# opl2msx_v1_1.net
KiCad netlist of a schematic drawn in EAGLE
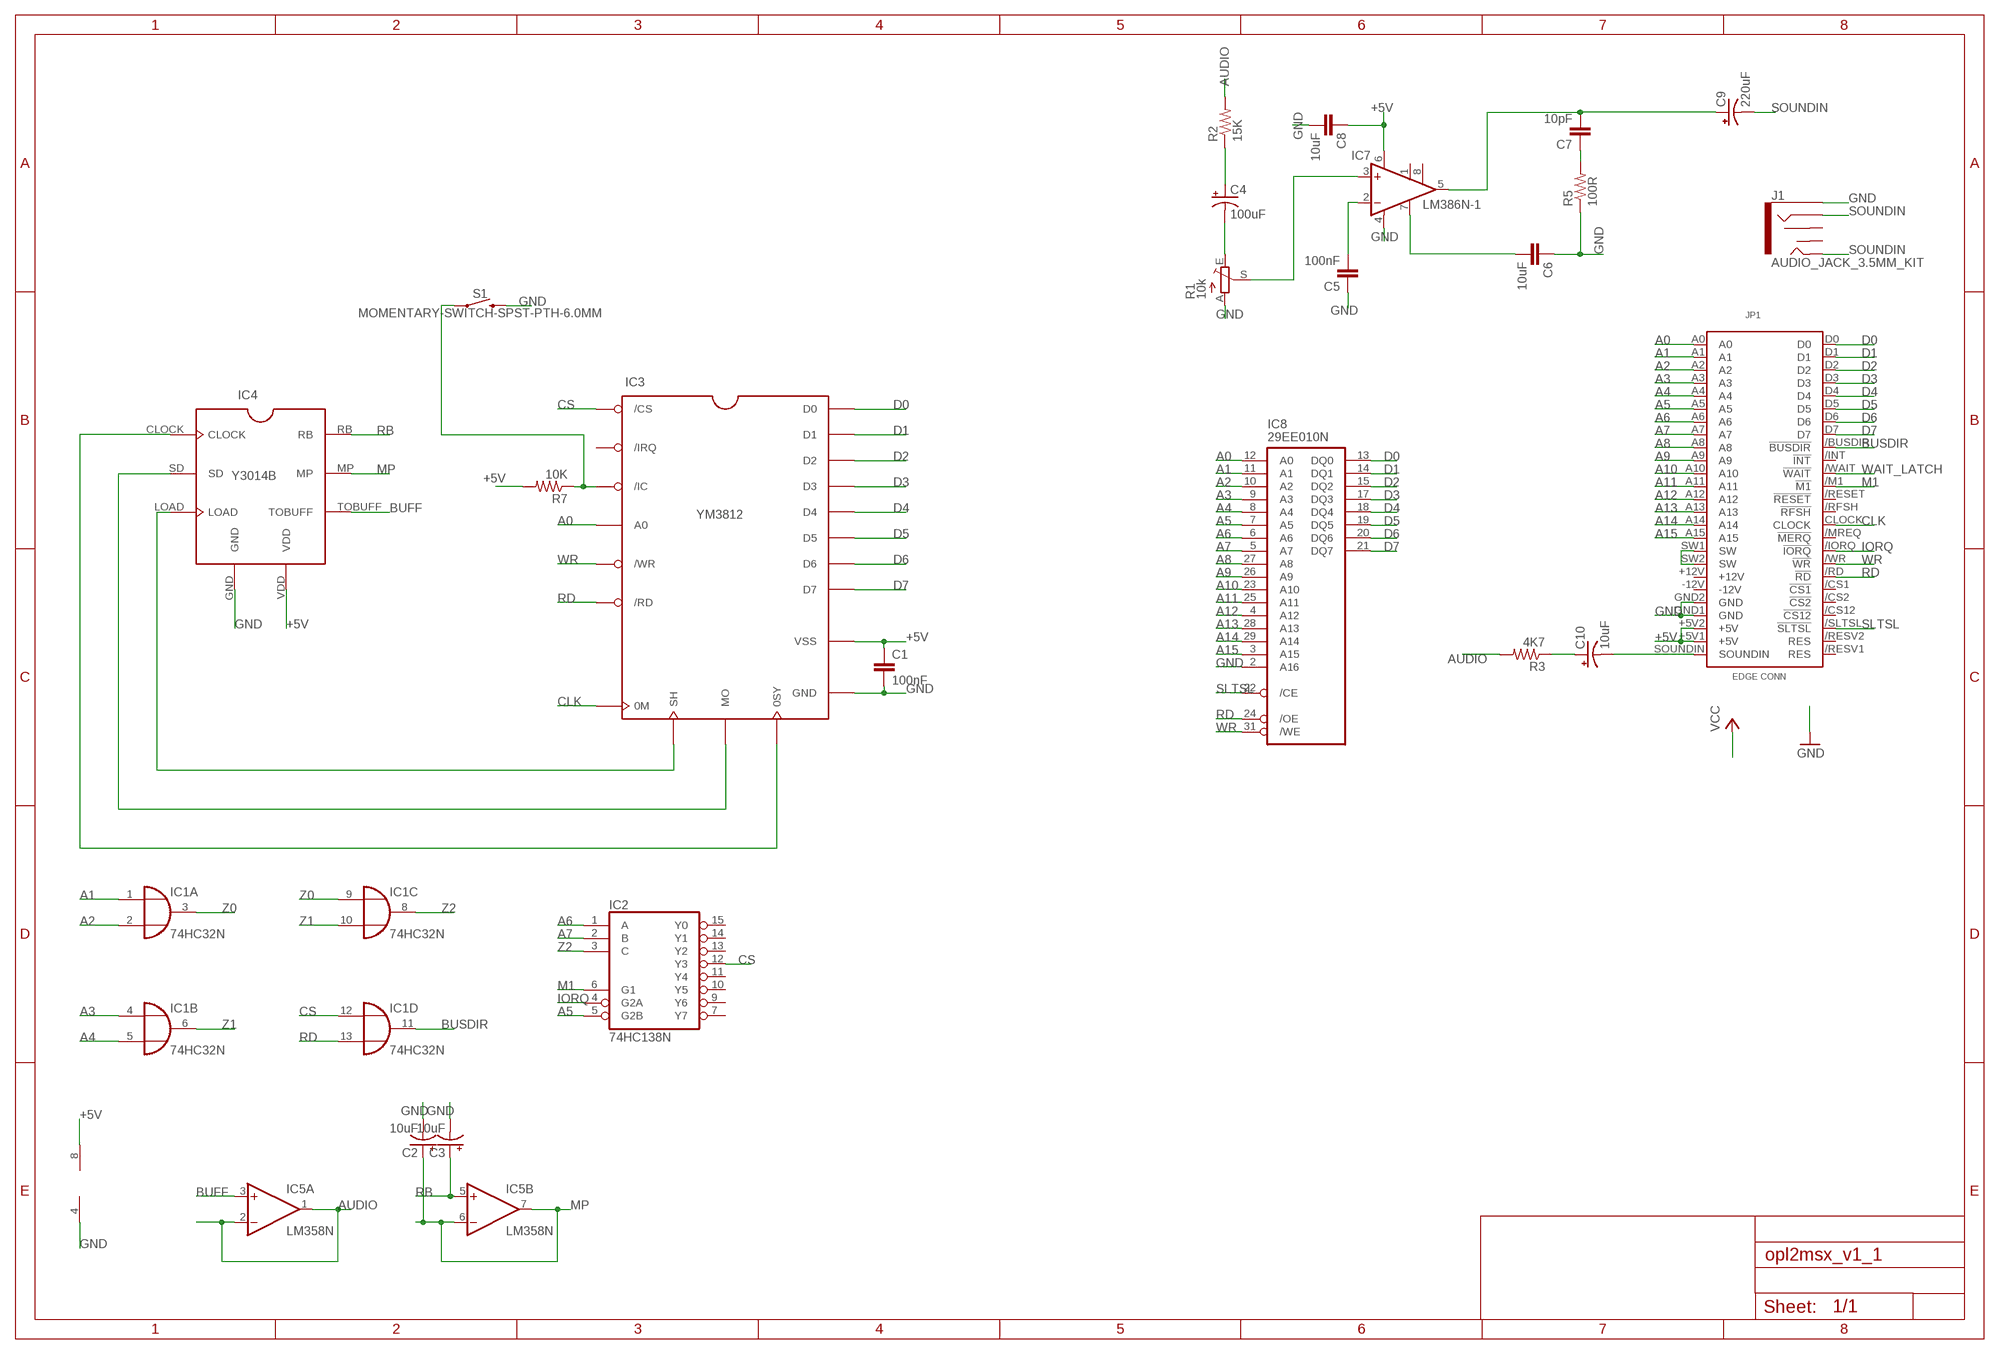
[diagram p0: schematic, sheet 1]

(export (version "E")
  (design (tool "Eeschema 10.0.6"))
  (components
    (comp (ref "C1")
      (value "100nF")
      (footprint "eagle-import:C050-024X044")
      (libsource (lib "eagle-import") (part "C-EU050-024X044"))
    )
    (comp (ref "C2")
      (value "10uF")
      (footprint "eagle-import:E2,5-6")
      (libsource (lib "eagle-import") (part "CPOL-USE2.5-6"))
    )
    (comp (ref "C3")
      (value "10uF")
      (footprint "eagle-import:E2,5-6")
      (libsource (lib "eagle-import") (part "CPOL-USE2.5-6"))
    )
    (comp (ref "C4")
      (value "100uF")
      (footprint "eagle-import:E2,5-6")
      (libsource (lib "eagle-import") (part "CPOL-USE2.5-6"))
    )
    (comp (ref "C5")
      (value "100nF")
      (footprint "eagle-import:C050-024X044")
      (libsource (lib "eagle-import") (part "C-EU050-024X044"))
    )
    (comp (ref "C6")
      (value "10uF")
      (footprint "eagle-import:C050-024X044")
      (libsource (lib "eagle-import") (part "C-EU050-024X044"))
    )
    (comp (ref "C7")
      (value "10pF")
      (footprint "eagle-import:C050-024X044")
      (libsource (lib "eagle-import") (part "C-EU050-024X044"))
    )
    (comp (ref "C8")
      (value "10uF")
      (footprint "eagle-import:C050-024X044")
      (libsource (lib "eagle-import") (part "C-EU050-024X044"))
    )
    (comp (ref "C9")
      (value "220uF")
      (footprint "eagle-import:E2,5-6")
      (libsource (lib "eagle-import") (part "CPOL-USE2.5-6"))
    )
    (comp (ref "C10")
      (value "10uF")
      (footprint "eagle-import:E2,5-6")
      (libsource (lib "eagle-import") (part "CPOL-USE2.5-6"))
    )
    (comp (ref "IC1")
      (value "74HC32N")
      (footprint "eagle-import:DIL14")
      (libsource (lib "eagle-import") (part "7432NHC"))
    )
    (comp (ref "IC2")
      (value "74HC138N")
      (footprint "eagle-import:DIL16")
      (libsource (lib "eagle-import") (part "74138NHC"))
    )
    (comp (ref "IC3")
      (value "YM3812")
      (footprint "eagle-import:YM3812")
      (libsource (lib "eagle-import") (part "YM3812-DIP24"))
    )
    (comp (ref "IC4")
      (value "Y3014B")
      (footprint "eagle-import:YM3014B")
      (libsource (lib "eagle-import") (part "YM3014B-DIP8"))
    )
    (comp (ref "IC5")
      (value "LM358N")
      (footprint "eagle-import:DIL08")
      (libsource (lib "eagle-import") (part "LM358N"))
    )
    (comp (ref "IC7")
      (value "LM386N-1")
      (footprint "eagle-import:DIL08")
      (libsource (lib "eagle-import") (part "LM386?-N1"))
    )
    (comp (ref "IC8")
      (value "29EE010N")
      (footprint "eagle-import:DIL32-6")
      (libsource (lib "eagle-import") (part "29XE010N"))
    )
    (comp (ref "J1")
      (value "AUDIO_JACK_3.5MM_KIT")
      (footprint "eagle-import:AUDIO-JACK-KIT")
      (libsource (lib "eagle-import") (part "AUDIO_JACK_3.5MM_KIT"))
    )
    (comp (ref "JP1")
      (value "MSXCART")
      (footprint "eagle-import:PATOLA-MSX-SEEED")
      (libsource (lib "eagle-import") (part "MSXCART"))
    )
    (comp (ref "R1")
      (value "10k")
      (footprint "eagle-import:CA6V")
      (libsource (lib "eagle-import") (part "TRIM_EU-CA6V"))
    )
    (comp (ref "R2")
      (value "15K")
      (footprint "eagle-import:0207_10")
      (libsource (lib "eagle-import") (part "R-US_0207/10"))
    )
    (comp (ref "R3")
      (value "4K7")
      (footprint "eagle-import:0207_10")
      (libsource (lib "eagle-import") (part "R-US_0207/10"))
    )
    (comp (ref "R5")
      (value "100R")
      (footprint "eagle-import:0207_10")
      (libsource (lib "eagle-import") (part "R-US_0207/10"))
    )
    (comp (ref "R7")
      (value "10K")
      (footprint "eagle-import:0207_10")
      (libsource (lib "eagle-import") (part "R-US_0207/10"))
    )
    (comp (ref "S1")
      (value "MOMENTARY-SWITCH-SPST-PTH-6.0MM")
      (footprint "eagle-import:TACTILE_SWITCH_PTH_6.0MM")
      (libsource (lib "eagle-import") (part "MOMENTARY-SWITCH-SPST-PTH-6.0MM"))
    )
  )
  (nets
    (net (code "1") (name "/+5V") (class "Default")
      (node (ref "C1") (pin "1") (pinfunction "1_1") (pintype "passive"))
      (node (ref "C8") (pin "1") (pinfunction "1_1") (pintype "passive"))
      (node (ref "IC3") (pin "VSS") (pinfunction "VSS_VSS") (pintype "power_in"))
      (node (ref "IC4") (pin "VDD") (pinfunction "VDD_VDD") (pintype "power_in"))
      (node (ref "IC5") (pin "8") (pinfunction "V+_8") (pintype "power_in"))
      (node (ref "IC7") (pin "6") (pinfunction "VS_6") (pintype "power_in"))
      (node (ref "JP1") (pin "+5V1") (pinfunction "+5V_+5V1") (pintype "power_in"))
      (node (ref "JP1") (pin "+5V2") (pinfunction "+5V_+5V2") (pintype "power_in"))
      (node (ref "R7") (pin "2") (pinfunction "2_2") (pintype "passive"))
    )
    (net (code "2") (name "/+12V") (class "Default")
      (node (ref "JP1") (pin "+12V") (pinfunction "+12V_+12V") (pintype "power_in"))
    )
    (net (code "3") (name "/-12V") (class "Default")
      (node (ref "JP1") (pin "-12V") (pinfunction "-12V_-12V") (pintype "power_in"))
    )
    (net (code "4") (name "/A0") (class "Default")
      (node (ref "IC3") (pin "A0") (pinfunction "A0_A0") (pintype "bidirectional"))
      (node (ref "IC8") (pin "12") (pinfunction "A0_12") (pintype "input"))
      (node (ref "JP1") (pin "A0") (pinfunction "A0_A0") (pintype "output"))
    )
    (net (code "5") (name "/A1") (class "Default")
      (node (ref "IC1") (pin "1") (pinfunction "I0_1") (pintype "input"))
      (node (ref "IC8") (pin "11") (pinfunction "A1_11") (pintype "input"))
      (node (ref "JP1") (pin "A1") (pinfunction "A1_A1") (pintype "output"))
    )
    (net (code "6") (name "/A2") (class "Default")
      (node (ref "IC1") (pin "2") (pinfunction "I1_2") (pintype "input"))
      (node (ref "IC8") (pin "10") (pinfunction "A2_10") (pintype "input"))
      (node (ref "JP1") (pin "A2") (pinfunction "A2_A2") (pintype "output"))
    )
    (net (code "7") (name "/A3") (class "Default")
      (node (ref "IC1") (pin "4") (pinfunction "I0_4") (pintype "input"))
      (node (ref "IC8") (pin "9") (pinfunction "A3_9") (pintype "input"))
      (node (ref "JP1") (pin "A3") (pinfunction "A3_A3") (pintype "output"))
    )
    (net (code "8") (name "/A4") (class "Default")
      (node (ref "IC1") (pin "5") (pinfunction "I1_5") (pintype "input"))
      (node (ref "IC8") (pin "8") (pinfunction "A4_8") (pintype "input"))
      (node (ref "JP1") (pin "A4") (pinfunction "A4_A4") (pintype "output"))
    )
    (net (code "9") (name "/A5") (class "Default")
      (node (ref "IC2") (pin "5") (pinfunction "G2B_5") (pintype "input"))
      (node (ref "IC8") (pin "7") (pinfunction "A5_7") (pintype "input"))
      (node (ref "JP1") (pin "A5") (pinfunction "A5_A5") (pintype "output"))
    )
    (net (code "10") (name "/A6") (class "Default")
      (node (ref "IC2") (pin "1") (pinfunction "A_1") (pintype "input"))
      (node (ref "IC8") (pin "6") (pinfunction "A6_6") (pintype "input"))
      (node (ref "JP1") (pin "A6") (pinfunction "A6_A6") (pintype "output"))
    )
    (net (code "11") (name "/A7") (class "Default")
      (node (ref "IC2") (pin "2") (pinfunction "B_2") (pintype "input"))
      (node (ref "IC8") (pin "5") (pinfunction "A7_5") (pintype "input"))
      (node (ref "JP1") (pin "A7") (pinfunction "A7_A7") (pintype "output"))
    )
    (net (code "12") (name "/A8") (class "Default")
      (node (ref "IC8") (pin "27") (pinfunction "A8_27") (pintype "input"))
      (node (ref "JP1") (pin "A8") (pinfunction "A8_A8") (pintype "output"))
    )
    (net (code "13") (name "/A9") (class "Default")
      (node (ref "IC8") (pin "26") (pinfunction "A9_26") (pintype "input"))
      (node (ref "JP1") (pin "A9") (pinfunction "A9_A9") (pintype "output"))
    )
    (net (code "14") (name "/A10") (class "Default")
      (node (ref "IC8") (pin "23") (pinfunction "A10_23") (pintype "input"))
      (node (ref "JP1") (pin "A10") (pinfunction "A10_A10") (pintype "output"))
    )
    (net (code "15") (name "/A11") (class "Default")
      (node (ref "IC8") (pin "25") (pinfunction "A11_25") (pintype "input"))
      (node (ref "JP1") (pin "A11") (pinfunction "A11_A11") (pintype "output"))
    )
    (net (code "16") (name "/A12") (class "Default")
      (node (ref "IC8") (pin "4") (pinfunction "A12_4") (pintype "input"))
      (node (ref "JP1") (pin "A12") (pinfunction "A12_A12") (pintype "output"))
    )
    (net (code "17") (name "/A13") (class "Default")
      (node (ref "IC8") (pin "28") (pinfunction "A13_28") (pintype "input"))
      (node (ref "JP1") (pin "A13") (pinfunction "A13_A13") (pintype "output"))
    )
    (net (code "18") (name "/A14") (class "Default")
      (node (ref "IC8") (pin "29") (pinfunction "A14_29") (pintype "input"))
      (node (ref "JP1") (pin "A14") (pinfunction "A14_A14") (pintype "output"))
    )
    (net (code "19") (name "/A15") (class "Default")
      (node (ref "IC8") (pin "3") (pinfunction "A15_3") (pintype "input"))
      (node (ref "JP1") (pin "A15") (pinfunction "A15_A15") (pintype "output"))
    )
    (net (code "20") (name "/AUDIO") (class "Default")
      (node (ref "IC5") (pin "1") (pinfunction "OUT_1") (pintype "output"))
      (node (ref "IC5") (pin "2") (pinfunction "-IN_2") (pintype "input"))
      (node (ref "R2") (pin "2") (pinfunction "2_2") (pintype "passive"))
      (node (ref "R3") (pin "2") (pinfunction "2_2") (pintype "passive"))
    )
    (net (code "21") (name "/BUFF") (class "Default")
      (node (ref "IC4") (pin "TOBUFF") (pinfunction "TOBUFF_TOBUFF") (pintype "bidirectional"))
      (node (ref "IC5") (pin "3") (pinfunction "+IN_3") (pintype "input"))
    )
    (net (code "22") (name "/BUSDIR") (class "Default")
      (node (ref "IC1") (pin "11") (pinfunction "O_11") (pintype "output"))
      (node (ref "JP1") (pin "/BUSDIR") (pinfunction "~{BUSDIR}_/BUSDIR") (pintype "input"))
    )
    (net (code "23") (name "/CLK") (class "Default")
      (node (ref "IC3") (pin "0M") (pinfunction "0M_0M") (pintype "bidirectional"))
      (node (ref "JP1") (pin "CLOCK") (pinfunction "CLOCK_CLOCK") (pintype "output"))
    )
    (net (code "24") (name "/CS") (class "Default")
      (node (ref "IC1") (pin "12") (pinfunction "I0_12") (pintype "input"))
      (node (ref "IC2") (pin "12") (pinfunction "Y3_12") (pintype "output"))
      (node (ref "IC3") (pin "/CS") (pinfunction "/CS_/CS") (pintype "bidirectional"))
    )
    (net (code "25") (name "/D0") (class "Default")
      (node (ref "IC3") (pin "D0") (pinfunction "D0_D0") (pintype "power_in"))
      (node (ref "IC8") (pin "13") (pinfunction "DQ0_13") (pintype "bidirectional"))
      (node (ref "JP1") (pin "D0") (pinfunction "D0_D0") (pintype "bidirectional"))
    )
    (net (code "26") (name "/D1") (class "Default")
      (node (ref "IC3") (pin "D1") (pinfunction "D1_D1") (pintype "power_in"))
      (node (ref "IC8") (pin "14") (pinfunction "DQ1_14") (pintype "bidirectional"))
      (node (ref "JP1") (pin "D1") (pinfunction "D1_D1") (pintype "bidirectional"))
    )
    (net (code "27") (name "/D2") (class "Default")
      (node (ref "IC3") (pin "D2") (pinfunction "D2_D2") (pintype "power_in"))
      (node (ref "IC8") (pin "15") (pinfunction "DQ2_15") (pintype "bidirectional"))
      (node (ref "JP1") (pin "D2") (pinfunction "D2_D2") (pintype "bidirectional"))
    )
    (net (code "28") (name "/D3") (class "Default")
      (node (ref "IC3") (pin "D3") (pinfunction "D3_D3") (pintype "power_in"))
      (node (ref "IC8") (pin "17") (pinfunction "DQ3_17") (pintype "bidirectional"))
      (node (ref "JP1") (pin "D3") (pinfunction "D3_D3") (pintype "bidirectional"))
    )
    (net (code "29") (name "/D4") (class "Default")
      (node (ref "IC3") (pin "D4") (pinfunction "D4_D4") (pintype "power_in"))
      (node (ref "IC8") (pin "18") (pinfunction "DQ4_18") (pintype "bidirectional"))
      (node (ref "JP1") (pin "D4") (pinfunction "D4_D4") (pintype "bidirectional"))
    )
    (net (code "30") (name "/D5") (class "Default")
      (node (ref "IC3") (pin "D5") (pinfunction "D5_D5") (pintype "power_in"))
      (node (ref "IC8") (pin "19") (pinfunction "DQ5_19") (pintype "bidirectional"))
      (node (ref "JP1") (pin "D5") (pinfunction "D5_D5") (pintype "bidirectional"))
    )
    (net (code "31") (name "/D6") (class "Default")
      (node (ref "IC3") (pin "D6") (pinfunction "D6_D6") (pintype "power_in"))
      (node (ref "IC8") (pin "20") (pinfunction "DQ6_20") (pintype "bidirectional"))
      (node (ref "JP1") (pin "D6") (pinfunction "D6_D6") (pintype "bidirectional"))
    )
    (net (code "32") (name "/D7") (class "Default")
      (node (ref "IC3") (pin "D7") (pinfunction "D7_D7") (pintype "power_in"))
      (node (ref "IC8") (pin "21") (pinfunction "DQ7_21") (pintype "bidirectional"))
      (node (ref "JP1") (pin "D7") (pinfunction "D7_D7") (pintype "bidirectional"))
    )
    (net (code "33") (name "/IORQ") (class "Default")
      (node (ref "IC2") (pin "4") (pinfunction "G2A_4") (pintype "input"))
      (node (ref "JP1") (pin "/IORQ") (pinfunction "~{IORQ}_/IORQ") (pintype "output"))
    )
    (net (code "34") (name "/M1") (class "Default")
      (node (ref "IC2") (pin "6") (pinfunction "G1_6") (pintype "input"))
      (node (ref "JP1") (pin "/M1") (pinfunction "~{M1}_/M1") (pintype "output"))
    )
    (net (code "35") (name "/MP") (class "Default")
      (node (ref "C2") (pin "+") (pinfunction "+_+") (pintype "passive"))
      (node (ref "IC4") (pin "MP") (pinfunction "MP_MP") (pintype "bidirectional"))
      (node (ref "IC5") (pin "6") (pinfunction "-IN_6") (pintype "input"))
      (node (ref "IC5") (pin "7") (pinfunction "OUT_7") (pintype "output"))
    )
    (net (code "36") (name "/RB") (class "Default")
      (node (ref "C3") (pin "+") (pinfunction "+_+") (pintype "passive"))
      (node (ref "IC4") (pin "RB") (pinfunction "RB_RB") (pintype "bidirectional"))
      (node (ref "IC5") (pin "5") (pinfunction "+IN_5") (pintype "input"))
    )
    (net (code "37") (name "/RD") (class "Default")
      (node (ref "IC1") (pin "13") (pinfunction "I1_13") (pintype "input"))
      (node (ref "IC3") (pin "/RD") (pinfunction "/RD_/RD") (pintype "bidirectional"))
      (node (ref "IC8") (pin "24") (pinfunction "/OE_24") (pintype "input"))
      (node (ref "JP1") (pin "/RD") (pinfunction "~{RD}_/RD") (pintype "output"))
    )
    (net (code "38") (name "/SLTSL") (class "Default")
      (node (ref "IC8") (pin "22") (pinfunction "/CE_22") (pintype "input"))
      (node (ref "JP1") (pin "/SLTSL") (pinfunction "~{SLTSL}_/SLTSL") (pintype "output"))
    )
    (net (code "39") (name "/SOUNDIN") (class "Default")
      (node (ref "C9") (pin "-") (pinfunction "-_-") (pintype "passive"))
      (node (ref "J1") (pin "RING") (pinfunction "RING_RING") (pintype "bidirectional"))
      (node (ref "J1") (pin "TIP") (pinfunction "TIP_TIP") (pintype "bidirectional"))
    )
    (net (code "40") (name "/WAIT_LATCH") (class "Default")
      (node (ref "JP1") (pin "/WAIT") (pinfunction "~{WAIT}_/WAIT") (pintype "open_collector"))
    )
    (net (code "41") (name "/WR") (class "Default")
      (node (ref "IC3") (pin "/WR") (pinfunction "/WR_/WR") (pintype "bidirectional"))
      (node (ref "IC8") (pin "31") (pinfunction "/WE_31") (pintype "input"))
      (node (ref "JP1") (pin "/WR") (pinfunction "~{WR}_/WR") (pintype "output"))
    )
    (net (code "42") (name "/Z0") (class "Default")
      (node (ref "IC1") (pin "3") (pinfunction "O_3") (pintype "output"))
      (node (ref "IC1") (pin "9") (pinfunction "I0_9") (pintype "input"))
    )
    (net (code "43") (name "/Z1") (class "Default")
      (node (ref "IC1") (pin "10") (pinfunction "I1_10") (pintype "input"))
      (node (ref "IC1") (pin "6") (pinfunction "O_6") (pintype "output"))
    )
    (net (code "44") (name "/Z2") (class "Default")
      (node (ref "IC1") (pin "8") (pinfunction "O_8") (pintype "output"))
      (node (ref "IC2") (pin "3") (pinfunction "C_3") (pintype "input"))
    )
    (net (code "45") (name "GND") (class "Default")
      (node (ref "C1") (pin "2") (pinfunction "2_2") (pintype "passive"))
      (node (ref "C2") (pin "-") (pinfunction "-_-") (pintype "passive"))
      (node (ref "C3") (pin "-") (pinfunction "-_-") (pintype "passive"))
      (node (ref "C5") (pin "1") (pinfunction "1_1") (pintype "passive"))
      (node (ref "C6") (pin "1") (pinfunction "1_1") (pintype "passive"))
      (node (ref "C8") (pin "2") (pinfunction "2_2") (pintype "passive"))
      (node (ref "IC3") (pin "GND") (pinfunction "GND_GND") (pintype "power_in"))
      (node (ref "IC4") (pin "GND") (pinfunction "GND_GND") (pintype "power_in"))
      (node (ref "IC5") (pin "4") (pinfunction "V-_4") (pintype "power_in"))
      (node (ref "IC7") (pin "4") (pinfunction "GND_4") (pintype "power_in"))
      (node (ref "IC8") (pin "2") (pinfunction "A16_2") (pintype "input"))
      (node (ref "J1") (pin "SLEEVE") (pinfunction "SLEEVE_SLEEVE") (pintype "bidirectional"))
      (node (ref "JP1") (pin "GND1") (pinfunction "GND_GND1") (pintype "power_in"))
      (node (ref "JP1") (pin "GND2") (pinfunction "GND_GND2") (pintype "power_in"))
      (node (ref "R1") (pin "A") (pinfunction "A_A") (pintype "passive"))
      (node (ref "R5") (pin "1") (pinfunction "1_1") (pintype "passive"))
      (node (ref "S1") (pin "3") (pinfunction "2_3") (pintype "passive"))
    )
    (net (code "46") (name "Net-(C4-Pad+)") (class "Default")
      (node (ref "C4") (pin "+") (pinfunction "+_+") (pintype "passive"))
      (node (ref "R2") (pin "1") (pinfunction "1_1") (pintype "passive"))
    )
    (net (code "47") (name "Net-(C4-Pad-)") (class "Default")
      (node (ref "C4") (pin "-") (pinfunction "-_-") (pintype "passive"))
      (node (ref "R1") (pin "E") (pinfunction "E_E") (pintype "passive"))
    )
    (net (code "48") (name "Net-(C7-Pad1)") (class "Default")
      (node (ref "C7") (pin "1") (pinfunction "1_1") (pintype "passive"))
      (node (ref "R5") (pin "2") (pinfunction "2_2") (pintype "passive"))
    )
    (net (code "49") (name "Net-(C10-Pad+)") (class "Default")
      (node (ref "C10") (pin "+") (pinfunction "+_+") (pintype "passive"))
      (node (ref "R3") (pin "1") (pinfunction "1_1") (pintype "passive"))
    )
    (net (code "50") (name "Net-(C10-Pad-)") (class "Default")
      (node (ref "C10") (pin "-") (pinfunction "-_-") (pintype "passive"))
      (node (ref "JP1") (pin "SOUNDIN") (pinfunction "SOUNDIN_SOUNDIN") (pintype "passive"))
    )
    (net (code "51") (name "Net-(IC3-Pad0SY)") (class "Default")
      (node (ref "IC3") (pin "0SY") (pinfunction "0SY_0SY") (pintype "bidirectional"))
      (node (ref "IC4") (pin "CLOCK") (pinfunction "CLOCK_CLOCK") (pintype "bidirectional"))
    )
    (net (code "52") (name "Net-(IC3-PadMO)") (class "Default")
      (node (ref "IC3") (pin "MO") (pinfunction "MO_MO") (pintype "bidirectional"))
      (node (ref "IC4") (pin "SD") (pinfunction "SD_SD") (pintype "bidirectional"))
    )
    (net (code "53") (name "Net-(IC3-PadSH)") (class "Default")
      (node (ref "IC3") (pin "SH") (pinfunction "SH_SH") (pintype "bidirectional"))
      (node (ref "IC4") (pin "LOAD") (pinfunction "LOAD_LOAD") (pintype "bidirectional"))
    )
    (net (code "54") (name "Net-(IC3-Pad{slash}IC)") (class "Default")
      (node (ref "IC3") (pin "/IC") (pinfunction "/IC_/IC") (pintype "bidirectional"))
      (node (ref "R7") (pin "1") (pinfunction "1_1") (pintype "passive"))
      (node (ref "S1") (pin "1") (pinfunction "1_1") (pintype "passive"))
    )
    (net (code "55") (name "Net-(IC7-+IN)") (class "Default")
      (node (ref "IC7") (pin "3") (pinfunction "+IN_3") (pintype "input"))
      (node (ref "R1") (pin "S") (pinfunction "S_S") (pintype "passive"))
    )
    (net (code "56") (name "Net-(IC7--IN)") (class "Default")
      (node (ref "C5") (pin "2") (pinfunction "2_2") (pintype "passive"))
      (node (ref "IC7") (pin "2") (pinfunction "-IN_2") (pintype "input"))
    )
    (net (code "57") (name "Net-(IC7-BYPASS)") (class "Default")
      (node (ref "C6") (pin "2") (pinfunction "2_2") (pintype "passive"))
      (node (ref "IC7") (pin "7") (pinfunction "BYPASS_7") (pintype "passive"))
    )
    (net (code "58") (name "Net-(IC7-OUT)") (class "Default")
      (node (ref "C7") (pin "2") (pinfunction "2_2") (pintype "passive"))
      (node (ref "C9") (pin "+") (pinfunction "+_+") (pintype "passive"))
      (node (ref "IC7") (pin "5") (pinfunction "OUT_5") (pintype "output"))
    )
    (net (code "59") (name "Net-(JP1-SW-PadSW1)") (class "Default")
      (node (ref "JP1") (pin "SW1") (pinfunction "SW_SW1") (pintype "passive"))
      (node (ref "JP1") (pin "SW2") (pinfunction "SW_SW2") (pintype "passive"))
    )
    (net (code "61") (name "unconnected-(IC2A-Y0-Pad15)") (class "Default")
      (node (ref "IC2") (pin "15") (pinfunction "Y0_15") (pintype "output"))
    )
    (net (code "62") (name "unconnected-(IC2A-Y1-Pad14)") (class "Default")
      (node (ref "IC2") (pin "14") (pinfunction "Y1_14") (pintype "output"))
    )
    (net (code "63") (name "unconnected-(IC2A-Y2-Pad13)") (class "Default")
      (node (ref "IC2") (pin "13") (pinfunction "Y2_13") (pintype "output"))
    )
    (net (code "64") (name "unconnected-(IC2A-Y4-Pad11)") (class "Default")
      (node (ref "IC2") (pin "11") (pinfunction "Y4_11") (pintype "output"))
    )
    (net (code "65") (name "unconnected-(IC2A-Y5-Pad10)") (class "Default")
      (node (ref "IC2") (pin "10") (pinfunction "Y5_10") (pintype "output"))
    )
    (net (code "66") (name "unconnected-(IC2A-Y6-Pad9)") (class "Default")
      (node (ref "IC2") (pin "9") (pinfunction "Y6_9") (pintype "output"))
    )
    (net (code "67") (name "unconnected-(IC2A-Y7-Pad7)") (class "Default")
      (node (ref "IC2") (pin "7") (pinfunction "Y7_7") (pintype "output"))
    )
    (net (code "68") (name "unconnected-(IC3-Pad{slash}IRQ)") (class "Default")
      (node (ref "IC3") (pin "/IRQ") (pinfunction "/IRQ_/IRQ") (pintype "bidirectional"))
    )
    (net (code "69") (name "unconnected-(IC7-GAIN-Pad1)") (class "Default")
      (node (ref "IC7") (pin "1") (pinfunction "GAIN_1") (pintype "passive"))
    )
    (net (code "70") (name "unconnected-(IC7-GAIN-Pad8)") (class "Default")
      (node (ref "IC7") (pin "8") (pinfunction "GAIN_8") (pintype "passive"))
    )
    (net (code "71") (name "unconnected-(J1-PadRSH)") (class "Default")
      (node (ref "J1") (pin "RSH") (pinfunction "RSH_RSH") (pintype "bidirectional"))
    )
    (net (code "72") (name "unconnected-(J1-PadTSH)") (class "Default")
      (node (ref "J1") (pin "TSH") (pinfunction "TSH_TSH") (pintype "bidirectional"))
    )
    (net (code "73") (name "unconnected-(JP1-RES-Pad{slash}RESV1)") (class "Default")
      (node (ref "JP1") (pin "/RESV1") (pinfunction "RES_/RESV1") (pintype "no_connect"))
    )
    (net (code "74") (name "unconnected-(JP1-RES-Pad{slash}RESV2)") (class "Default")
      (node (ref "JP1") (pin "/RESV2") (pinfunction "RES_/RESV2") (pintype "no_connect"))
    )
    (net (code "75") (name "unconnected-(JP1-~{CS1}-Pad{slash}CS1)") (class "Default")
      (node (ref "JP1") (pin "/CS1") (pinfunction "~{CS1}_/CS1") (pintype "output"))
    )
    (net (code "76") (name "unconnected-(JP1-~{CS2}-Pad{slash}CS2)") (class "Default")
      (node (ref "JP1") (pin "/CS2") (pinfunction "~{CS2}_/CS2") (pintype "output"))
    )
    (net (code "77") (name "unconnected-(JP1-~{CS12}-Pad{slash}CS12)") (class "Default")
      (node (ref "JP1") (pin "/CS12") (pinfunction "~{CS12}_/CS12") (pintype "output"))
    )
    (net (code "78") (name "unconnected-(JP1-~{INT}-Pad{slash}INT)") (class "Default")
      (node (ref "JP1") (pin "/INT") (pinfunction "~{INT}_/INT") (pintype "open_collector"))
    )
    (net (code "79") (name "unconnected-(JP1-~{MERQ}-Pad{slash}MREQ)") (class "Default")
      (node (ref "JP1") (pin "/MREQ") (pinfunction "~{MERQ}_/MREQ") (pintype "output"))
    )
    (net (code "80") (name "unconnected-(JP1-~{RESET}-Pad{slash}RESET)") (class "Default")
      (node (ref "JP1") (pin "/RESET") (pinfunction "~{RESET}_/RESET") (pintype "output"))
    )
    (net (code "81") (name "unconnected-(JP1-~{RFSH}-Pad{slash}RFSH)") (class "Default")
      (node (ref "JP1") (pin "/RFSH") (pinfunction "~{RFSH}_/RFSH") (pintype "output"))
    )
  )
)
